# MOSFET_PCB.net
KiCad netlist of a schematic drawn in EAGLE
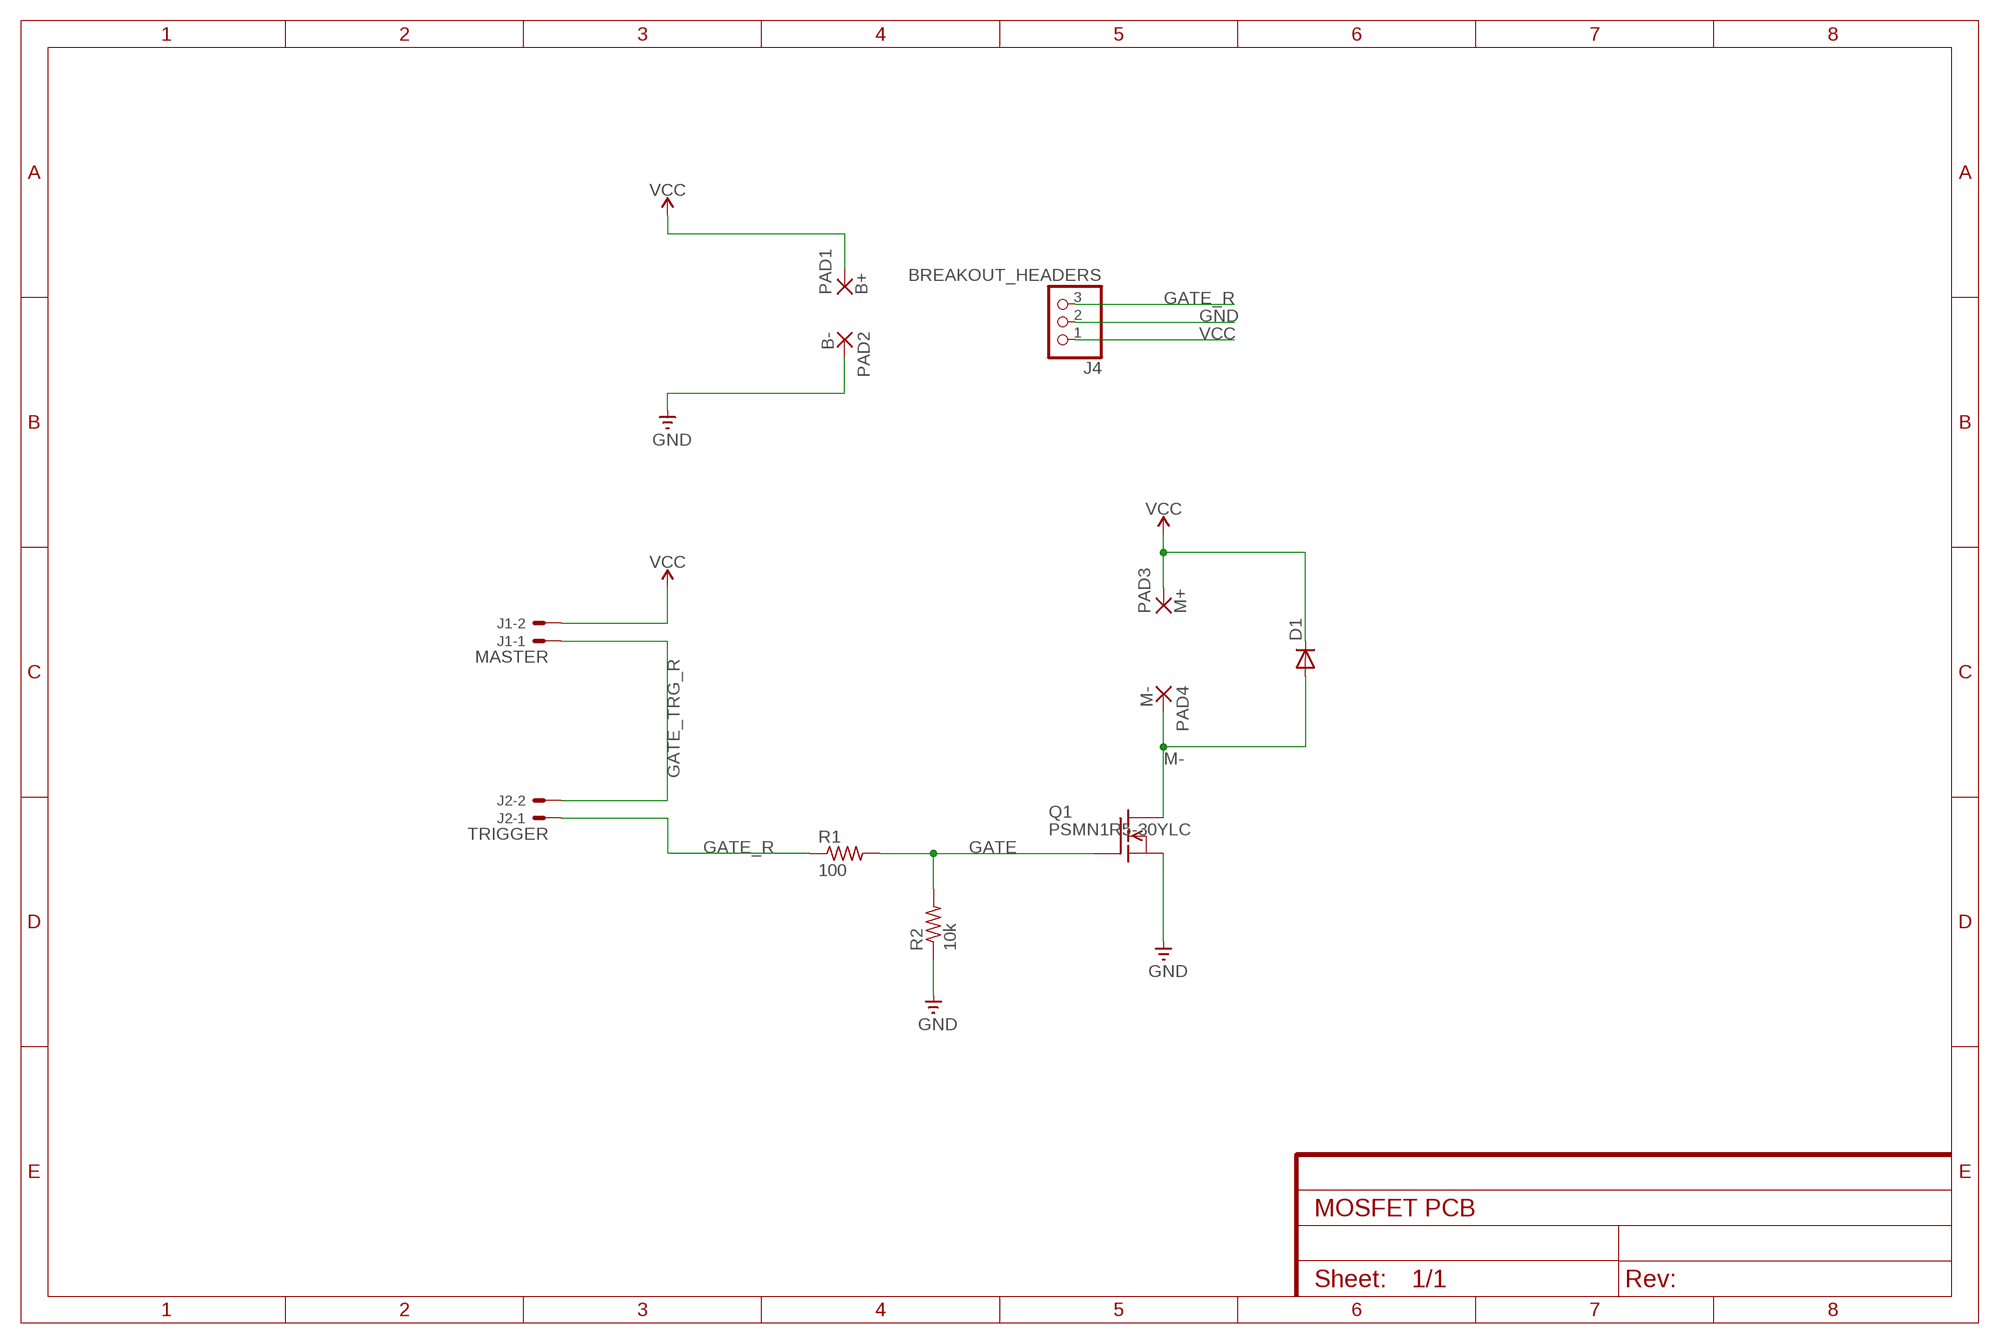
[diagram p0: schematic, sheet 1]

(export (version "E")
  (design (tool "Eeschema 10.0.6"))
  (components
    (comp (ref "D1")
      (value "S2A")
      (footprint "eagle-import:DO214AA")
      (fields (field (name "MF") "Fairchild"))
      (libsource (lib "eagle-import") (part "S2A"))
    )
    (comp (ref "J1")
      (value "MASTER")
      (footprint "eagle-import:JST-XH-02-PACKAGE-ROUND-PAD")
      (libsource (lib "eagle-import") (part "JST-XH-02-PIN-ROUND-PAD"))
    )
    (comp (ref "J2")
      (value "TRIGGER")
      (footprint "eagle-import:JST-XH-02-PACKAGE-ROUND-PAD")
      (libsource (lib "eagle-import") (part "JST-XH-02-PIN-ROUND-PAD"))
    )
    (comp (ref "J4")
      (value "BREAKOUT_HEADERS")
      (footprint "eagle-import:1X03")
      (libsource (lib "eagle-import") (part "PINHD-1X3"))
    )
    (comp (ref "PAD1")
      (value "B+")
      (footprint "eagle-import:5-2,5")
      (libsource (lib "eagle-import") (part "WIREPADSMD5-2,5"))
    )
    (comp (ref "PAD2")
      (value "B-")
      (footprint "eagle-import:5-2,5")
      (libsource (lib "eagle-import") (part "WIREPADSMD5-2,5"))
    )
    (comp (ref "PAD3")
      (value "M+")
      (footprint "eagle-import:5-2,5")
      (libsource (lib "eagle-import") (part "WIREPADSMD5-2,5"))
    )
    (comp (ref "PAD4")
      (value "M-")
      (footprint "eagle-import:5-2,5")
      (libsource (lib "eagle-import") (part "WIREPADSMD5-2,5"))
    )
    (comp (ref "Q1")
      (value "PSMN1R5-30YLC")
      (footprint "eagle-import:TO127P600X120-5N")
      (libsource (lib "eagle-import") (part "PSMN1R5-30YLC"))
    )
    (comp (ref "R1")
      (value "100")
      (footprint "eagle-import:M0805")
      (libsource (lib "eagle-import") (part "R-US_M0805"))
    )
    (comp (ref "R2")
      (value "10k")
      (footprint "eagle-import:M0805")
      (libsource (lib "eagle-import") (part "R-US_M0805"))
    )
  )
  (nets
    (net (code "1") (name "/GATE") (class "Default")
      (node (ref "Q1") (pin "4") (pinfunction "G_4") (pintype "passive"))
      (node (ref "R1") (pin "2") (pinfunction "2_2") (pintype "passive"))
      (node (ref "R2") (pin "2") (pinfunction "2_2") (pintype "passive"))
    )
    (net (code "2") (name "/GATE_R") (class "Default")
      (node (ref "J2") (pin "1") (pinfunction "S_1") (pintype "passive"))
      (node (ref "J4") (pin "3") (pinfunction "3_3") (pintype "passive"))
      (node (ref "R1") (pin "1") (pinfunction "1_1") (pintype "passive"))
    )
    (net (code "3") (name "/GATE_TRG_R") (class "Default")
      (node (ref "J1") (pin "1") (pinfunction "S_1") (pintype "passive"))
      (node (ref "J2") (pin "2") (pinfunction "S_2") (pintype "passive"))
    )
    (net (code "4") (name "/M-") (class "Default")
      (node (ref "D1") (pin "A") (pinfunction "A_A") (pintype "passive"))
      (node (ref "PAD4") (pin "1") (pinfunction "P_1") (pintype "passive"))
      (node (ref "Q1") (pin "5") (pinfunction "D_5") (pintype "passive"))
    )
    (net (code "5") (name "GND") (class "Default")
      (node (ref "J4") (pin "2") (pinfunction "2_2") (pintype "passive"))
      (node (ref "PAD2") (pin "1") (pinfunction "P_1") (pintype "passive"))
      (node (ref "Q1") (pin "1") (pinfunction "S_1") (pintype "passive"))
      (node (ref "Q1") (pin "2") (pinfunction "S_2") (pintype "passive"))
      (node (ref "Q1") (pin "3") (pinfunction "S_3") (pintype "passive"))
      (node (ref "R2") (pin "1") (pinfunction "1_1") (pintype "passive"))
    )
    (net (code "6") (name "VCC") (class "Default")
      (node (ref "D1") (pin "C") (pinfunction "C_C") (pintype "passive"))
      (node (ref "J1") (pin "2") (pinfunction "S_2") (pintype "passive"))
      (node (ref "J4") (pin "1") (pinfunction "1_1") (pintype "passive"))
      (node (ref "PAD1") (pin "1") (pinfunction "P_1") (pintype "passive"))
      (node (ref "PAD3") (pin "1") (pinfunction "P_1") (pintype "passive"))
    )
  )
)
